# Lilypad_Minifade.net
KiCad netlist of a schematic drawn in EAGLE
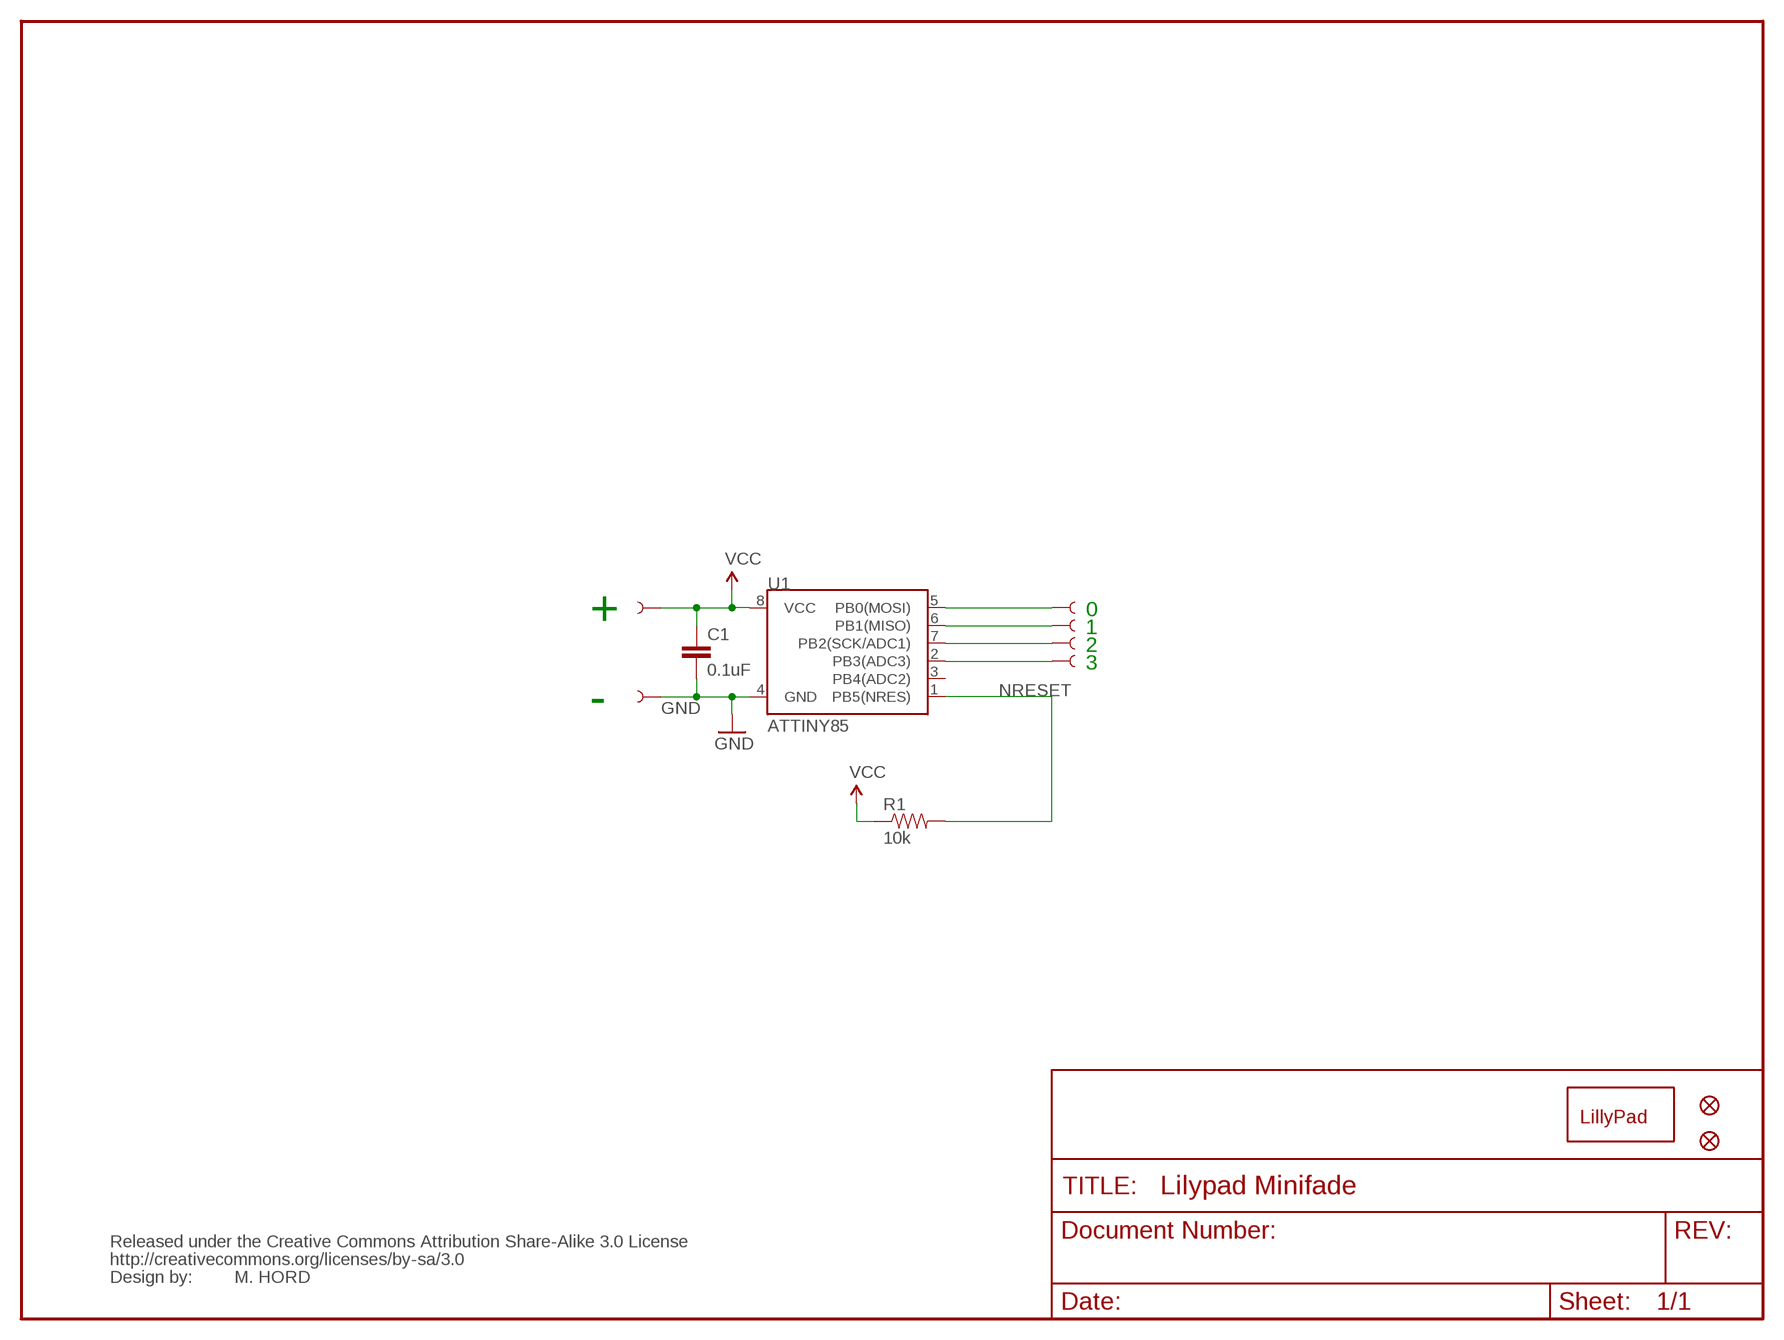
[diagram p0: schematic, sheet 1]

(export (version "E")
  (design (tool "Eeschema 10.0.6"))
  (components
    (comp (ref "C1")
      (value "0.1uF")
      (footprint "eagle-import:0402-CAP")
      (libsource (lib "eagle-import") (part "CAP0402-CAP"))
    )
    (comp (ref "JP1")
      (value "FIDUCIALUFIDUCIAL")
      (footprint "eagle-import:MICRO-FIDUCIAL")
      (libsource (lib "eagle-import") (part "FIDUCIALUFIDUCIAL"))
    )
    (comp (ref "JP2")
      (value "FIDUCIALUFIDUCIAL")
      (footprint "eagle-import:MICRO-FIDUCIAL")
      (libsource (lib "eagle-import") (part "FIDUCIALUFIDUCIAL"))
    )
    (comp (ref "R1")
      (value "10k")
      (footprint "eagle-import:0402-RES")
      (libsource (lib "eagle-import") (part "RESISTOR0402-RES"))
    )
    (comp (ref "U$1")
      (value "CREATIVE_COMMONS")
      (footprint "eagle-import:CREATIVE_COMMONS")
      (libsource (lib "eagle-import") (part "CREATIVE_COMMONS"))
    )
    (comp (ref "U$2")
      (value "SEWTAP6")
      (footprint "eagle-import:PETAL-SMALL-2SIDE")
      (libsource (lib "eagle-import") (part "SEWTAP6"))
    )
    (comp (ref "U$3")
      (value "SEWTAP6")
      (footprint "eagle-import:PETAL-SMALL-2SIDE")
      (libsource (lib "eagle-import") (part "SEWTAP6"))
    )
    (comp (ref "U$4")
      (value "SEWTAP6")
      (footprint "eagle-import:PETAL-SMALL-2SIDE")
      (libsource (lib "eagle-import") (part "SEWTAP6"))
    )
    (comp (ref "U$5")
      (value "SEWTAP6")
      (footprint "eagle-import:PETAL-SMALL-2SIDE")
      (libsource (lib "eagle-import") (part "SEWTAP6"))
    )
    (comp (ref "U$6")
      (value "SEWTAP6")
      (footprint "eagle-import:PETAL-SMALL-2SIDE")
      (libsource (lib "eagle-import") (part "SEWTAP6"))
    )
    (comp (ref "U$7")
      (value "SEWTAP6")
      (footprint "eagle-import:PETAL-SMALL-2SIDE")
      (libsource (lib "eagle-import") (part "SEWTAP6"))
    )
    (comp (ref "U$8")
      (value "LOGO-LPL")
      (footprint "eagle-import:LOGO-L")
      (libsource (lib "eagle-import") (part "LOGO-LPL"))
    )
    (comp (ref "U1")
      (value "ATTINY85")
      (footprint "eagle-import:SO08-EIAJ")
      (libsource (lib "eagle-import") (part "ATTINY45"))
    )
  )
  (nets
    (net (code "1") (name "/NRESET") (class "Default")
      (node (ref "R1") (pin "2") (pinfunction "2_2") (pintype "passive"))
      (node (ref "U1") (pin "1") (pinfunction "PB5(NRES)_1") (pintype "bidirectional"))
    )
    (net (code "2") (name "GND") (class "Default")
      (node (ref "C1") (pin "2") (pinfunction "2_2") (pintype "passive"))
      (node (ref "U$2") (pin "1") (pinfunction "1_1") (pintype "bidirectional"))
      (node (ref "U1") (pin "4") (pinfunction "GND_4") (pintype "bidirectional"))
    )
    (net (code "3") (name "Net-(U1-PB0(MOSI))") (class "Default")
      (node (ref "U$7") (pin "1") (pinfunction "1_1") (pintype "bidirectional"))
      (node (ref "U1") (pin "5") (pinfunction "PB0(MOSI)_5") (pintype "bidirectional"))
    )
    (net (code "4") (name "Net-(U1-PB1(MISO))") (class "Default")
      (node (ref "U$3") (pin "1") (pinfunction "1_1") (pintype "bidirectional"))
      (node (ref "U1") (pin "6") (pinfunction "PB1(MISO)_6") (pintype "bidirectional"))
    )
    (net (code "5") (name "Net-(U1-PB2(SCK{slash}ADC1))") (class "Default")
      (node (ref "U$4") (pin "1") (pinfunction "1_1") (pintype "bidirectional"))
      (node (ref "U1") (pin "7") (pinfunction "PB2(SCK/ADC1)_7") (pintype "bidirectional"))
    )
    (net (code "6") (name "Net-(U1-PB3(ADC3))") (class "Default")
      (node (ref "U$6") (pin "1") (pinfunction "1_1") (pintype "bidirectional"))
      (node (ref "U1") (pin "2") (pinfunction "PB3(ADC3)_2") (pintype "bidirectional"))
    )
    (net (code "7") (name "VCC") (class "Default")
      (node (ref "C1") (pin "1") (pinfunction "1_1") (pintype "passive"))
      (node (ref "R1") (pin "1") (pinfunction "1_1") (pintype "passive"))
      (node (ref "U$5") (pin "1") (pinfunction "1_1") (pintype "bidirectional"))
      (node (ref "U1") (pin "8") (pinfunction "VCC_8") (pintype "bidirectional"))
    )
    (net (code "8") (name "unconnected-(U1-PB4(ADC2)-Pad3)") (class "Default")
      (node (ref "U1") (pin "3") (pinfunction "PB4(ADC2)_3") (pintype "bidirectional"))
    )
  )
)
